# MCU.net
KiCad netlist of a schematic drawn in Altium Designer
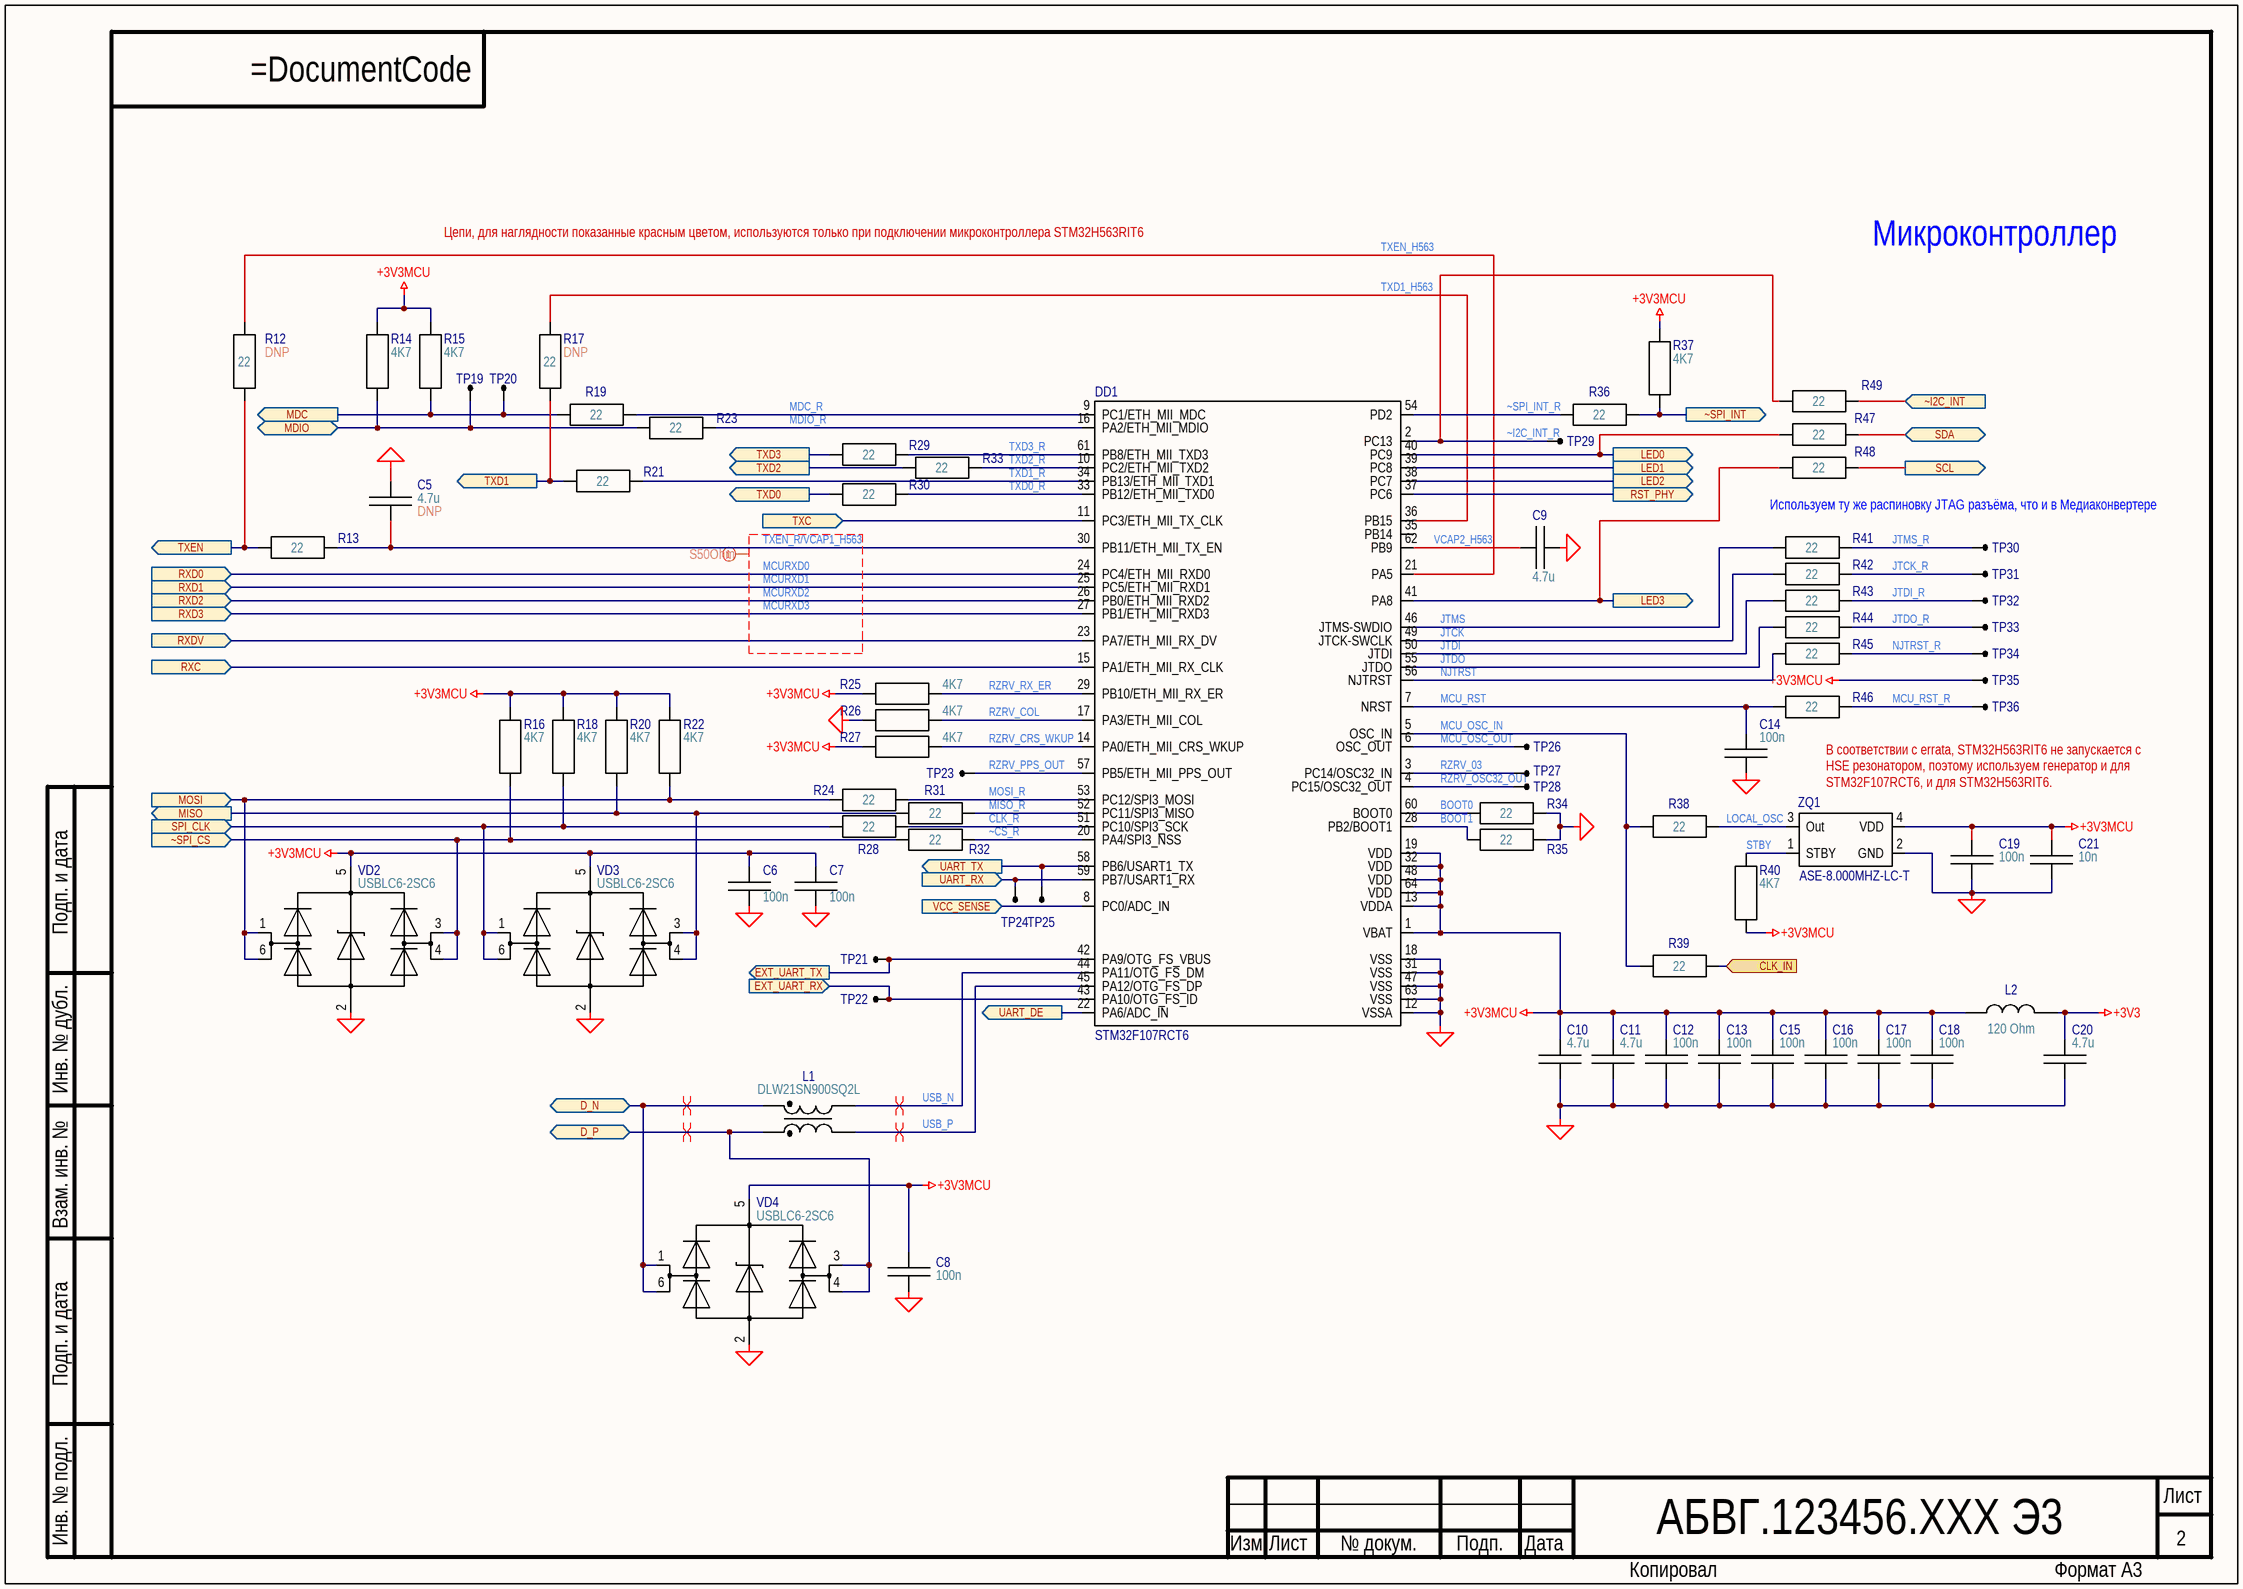
[diagram p0: MCU.SchDoc]

(export (version "E")
  (design (tool "Eeschema 10.0.6"))
  (components
    (comp (ref "C5")
      (value "4.7u")
      (footprint "C0603")
      (description "Чип-конденсатор 4,7 мкФ 10% 16 В X5R 0603")
      (fields
        (field (name "MANUFACTURER PART NUMBER") "CC0603KRX5R7BB475")
        (field (name "MANUFACTURER") "Yageo")
      )
      (libsource (lib "ums") (part "C0603"))
    )
    (comp (ref "C6")
      (value "100n")
      (footprint "C0402")
      (description "Чип-конденсатор 100 нФ 10% 50 В X7R 0402")
      (fields
        (field (name "MANUFACTURER PART NUMBER") "CC0402KRX7R9BB104")
        (field (name "MANUFACTURER") "Yageo")
      )
      (libsource (lib "ums") (part "C0402"))
    )
    (comp (ref "C7")
      (value "100n")
      (footprint "C0402")
      (description "Чип-конденсатор 100 нФ 10% 50 В X7R 0402")
      (fields
        (field (name "MANUFACTURER PART NUMBER") "CC0402KRX7R9BB104")
        (field (name "MANUFACTURER") "Yageo")
      )
      (libsource (lib "ums") (part "C0402"))
    )
    (comp (ref "C8")
      (value "100n")
      (footprint "C0402")
      (description "Чип-конденсатор 100 нФ 10% 50 В X7R 0402")
      (fields
        (field (name "MANUFACTURER PART NUMBER") "CC0402KRX7R9BB104")
        (field (name "MANUFACTURER") "Yageo")
      )
      (libsource (lib "ums") (part "C0402"))
    )
    (comp (ref "C9")
      (value "4.7u")
      (footprint "C0603")
      (description "Чип-конденсатор 4,7 мкФ 10% 16 В X5R 0603")
      (fields
        (field (name "MANUFACTURER PART NUMBER") "CC0603KRX5R7BB475")
        (field (name "MANUFACTURER") "Yageo")
      )
      (libsource (lib "ums") (part "C0603"))
    )
    (comp (ref "C10")
      (value "4.7u")
      (footprint "C0603")
      (description "Чип-конденсатор 4,7 мкФ 10% 16 В X5R 0603")
      (fields
        (field (name "MANUFACTURER PART NUMBER") "CC0603KRX5R7BB475")
        (field (name "MANUFACTURER") "Yageo")
      )
      (libsource (lib "ums") (part "C0603"))
    )
    (comp (ref "C11")
      (value "4.7u")
      (footprint "C0603")
      (description "Чип-конденсатор 4,7 мкФ 10% 16 В X5R 0603")
      (fields
        (field (name "MANUFACTURER PART NUMBER") "CC0603KRX5R7BB475")
        (field (name "MANUFACTURER") "Yageo")
      )
      (libsource (lib "ums") (part "C0603"))
    )
    (comp (ref "C12")
      (value "100n")
      (footprint "C0402")
      (description "Чип-конденсатор 100 нФ 10% 50 В X7R 0402")
      (fields
        (field (name "MANUFACTURER PART NUMBER") "CC0402KRX7R9BB104")
        (field (name "MANUFACTURER") "Yageo")
      )
      (libsource (lib "ums") (part "C0402"))
    )
    (comp (ref "C13")
      (value "100n")
      (footprint "C0402")
      (description "Чип-конденсатор 100 нФ 10% 50 В X7R 0402")
      (fields
        (field (name "MANUFACTURER PART NUMBER") "CC0402KRX7R9BB104")
        (field (name "MANUFACTURER") "Yageo")
      )
      (libsource (lib "ums") (part "C0402"))
    )
    (comp (ref "C14")
      (value "100n")
      (footprint "C0402")
      (description "Чип-конденсатор 100 нФ 10% 50 В X7R 0402")
      (fields
        (field (name "MANUFACTURER PART NUMBER") "CC0402KRX7R9BB104")
        (field (name "MANUFACTURER") "Yageo")
      )
      (libsource (lib "ums") (part "C0402"))
    )
    (comp (ref "C15")
      (value "100n")
      (footprint "C0402")
      (description "Чип-конденсатор 100 нФ 10% 50 В X7R 0402")
      (fields
        (field (name "MANUFACTURER PART NUMBER") "CC0402KRX7R9BB104")
        (field (name "MANUFACTURER") "Yageo")
      )
      (libsource (lib "ums") (part "C0402"))
    )
    (comp (ref "C16")
      (value "100n")
      (footprint "C0402")
      (description "Чип-конденсатор 100 нФ 10% 50 В X7R 0402")
      (fields
        (field (name "MANUFACTURER PART NUMBER") "CC0402KRX7R9BB104")
        (field (name "MANUFACTURER") "Yageo")
      )
      (libsource (lib "ums") (part "C0402"))
    )
    (comp (ref "C17")
      (value "100n")
      (footprint "C0402")
      (description "Чип-конденсатор 100 нФ 10% 50 В X7R 0402")
      (fields
        (field (name "MANUFACTURER PART NUMBER") "CC0402KRX7R9BB104")
        (field (name "MANUFACTURER") "Yageo")
      )
      (libsource (lib "ums") (part "C0402"))
    )
    (comp (ref "C18")
      (value "100n")
      (footprint "C0402")
      (description "Чип-конденсатор 100 нФ 10% 50 В X7R 0402")
      (fields
        (field (name "MANUFACTURER PART NUMBER") "CC0402KRX7R9BB104")
        (field (name "MANUFACTURER") "Yageo")
      )
      (libsource (lib "ums") (part "C0402"))
    )
    (comp (ref "C19")
      (value "100n")
      (footprint "C0402")
      (description "Чип-конденсатор 100 нФ 10% 50 В X7R 0402")
      (fields
        (field (name "MANUFACTURER PART NUMBER") "CC0402KRX7R9BB104")
        (field (name "MANUFACTURER") "Yageo")
      )
      (libsource (lib "ums") (part "C0402"))
    )
    (comp (ref "C20")
      (value "4.7u")
      (footprint "C0603")
      (description "Чип-конденсатор 4,7 мкФ 10% 16 В X5R 0603")
      (fields
        (field (name "MANUFACTURER PART NUMBER") "CC0603KRX5R7BB475")
        (field (name "MANUFACTURER") "Yageo")
      )
      (libsource (lib "ums") (part "C0603"))
    )
    (comp (ref "C21")
      (value "10n")
      (footprint "C0402")
      (description "Чип-конденсатор 10 нФ 10% 50 В X7R 0402")
      (fields
        (field (name "MANUFACTURER PART NUMBER") "CC0402KRX7R9BB103")
        (field (name "MANUFACTURER") "Yageo")
      )
      (libsource (lib "ums") (part "C0402"))
    )
    (comp (ref "DD1")
      (value "STM32F107RCT6")
      (footprint "LQFP-64-STM-Microcontroller")
      (description "Микроконтроллер ARM")
      (fields (field (name "MANUFACTURER") "ST Microelectronics"))
      (libsource (lib "ums") (part "STM32F107RCT6"))
    )
    (comp (ref "L1")
      (value "DLW21SN900SQ2L")
      (footprint "DLW21S")
      (description "Фильтр синфазный DLW21SN900SQ2L")
      (fields (field (name "MANUFACTURER") "Murata"))
      (libsource (lib "ums") (part "DLW21SN900SQ2L"))
    )
    (comp (ref "L2")
      (value "120 Ohm")
      (footprint "BLM18PG")
      (description "Фильтр индуктивный 120 Ом @ 100 МГц 2 А 0603")
      (fields
        (field (name "MANUFACTURER") "FENGHUA Advanced Technology")
        (field (name "MANUFACTURER PART NUMBER") "CBM160808U121T")
      )
      (libsource (lib "ums") (part "BLM18PG121SN1D"))
    )
    (comp (ref "R12")
      (value "22")
      (footprint "R0402")
      (description "Чип-резистор 22 Ом 1% 0402")
      (fields
        (field (name "MANUFACTURER PART NUMBER") "RC0402FR-0722RL")
        (field (name "MANUFACTURER") "Yageo")
      )
      (libsource (lib "ums") (part "R0402_tooth_1"))
    )
    (comp (ref "R13")
      (value "22")
      (footprint "R0402")
      (description "Чип-резистор 22 Ом 1% 0402")
      (fields
        (field (name "MANUFACTURER PART NUMBER") "RC0402FR-0722RL")
        (field (name "MANUFACTURER") "Yageo")
      )
      (libsource (lib "ums") (part "R0402_tooth_1"))
    )
    (comp (ref "R14")
      (value "4K7")
      (footprint "R0402")
      (description "Чип-резистор 4,7 кОм 1% 0402")
      (fields
        (field (name "MANUFACTURER PART NUMBER") "RC0402FR-074K7L")
        (field (name "MANUFACTURER") "Yageo")
      )
      (libsource (lib "ums") (part "R0402"))
    )
    (comp (ref "R15")
      (value "4K7")
      (footprint "R0402")
      (description "Чип-резистор 4,7 кОм 1% 0402")
      (fields
        (field (name "MANUFACTURER PART NUMBER") "RC0402FR-074K7L")
        (field (name "MANUFACTURER") "Yageo")
      )
      (libsource (lib "ums") (part "R0402"))
    )
    (comp (ref "R16")
      (value "4K7")
      (footprint "R0402")
      (description "Чип-резистор 4,7 кОм 1% 0402")
      (fields
        (field (name "MANUFACTURER PART NUMBER") "RC0402FR-074K7L")
        (field (name "MANUFACTURER") "Yageo")
      )
      (libsource (lib "ums") (part "R0402"))
    )
    (comp (ref "R17")
      (value "22")
      (footprint "R0402")
      (description "Чип-резистор 22 Ом 1% 0402")
      (fields
        (field (name "MANUFACTURER PART NUMBER") "RC0402FR-0722RL")
        (field (name "MANUFACTURER") "Yageo")
      )
      (libsource (lib "ums") (part "R0402_tooth_1"))
    )
    (comp (ref "R18")
      (value "4K7")
      (footprint "R0402")
      (description "Чип-резистор 4,7 кОм 1% 0402")
      (fields
        (field (name "MANUFACTURER PART NUMBER") "RC0402FR-074K7L")
        (field (name "MANUFACTURER") "Yageo")
      )
      (libsource (lib "ums") (part "R0402"))
    )
    (comp (ref "R19")
      (value "22")
      (footprint "R0402")
      (description "Чип-резистор 22 Ом 1% 0402")
      (fields
        (field (name "MANUFACTURER PART NUMBER") "RC0402FR-0722RL")
        (field (name "MANUFACTURER") "Yageo")
      )
      (libsource (lib "ums") (part "R0402_tooth_1"))
    )
    (comp (ref "R20")
      (value "4K7")
      (footprint "R0402")
      (description "Чип-резистор 4,7 кОм 1% 0402")
      (fields
        (field (name "MANUFACTURER PART NUMBER") "RC0402FR-074K7L")
        (field (name "MANUFACTURER") "Yageo")
      )
      (libsource (lib "ums") (part "R0402"))
    )
    (comp (ref "R21")
      (value "22")
      (footprint "R0402")
      (description "Чип-резистор 22 Ом 1% 0402")
      (fields
        (field (name "MANUFACTURER PART NUMBER") "RC0402FR-0722RL")
        (field (name "MANUFACTURER") "Yageo")
      )
      (libsource (lib "ums") (part "R0402_tooth_1"))
    )
    (comp (ref "R22")
      (value "4K7")
      (footprint "R0402")
      (description "Чип-резистор 4,7 кОм 1% 0402")
      (fields
        (field (name "MANUFACTURER PART NUMBER") "RC0402FR-074K7L")
        (field (name "MANUFACTURER") "Yageo")
      )
      (libsource (lib "ums") (part "R0402"))
    )
    (comp (ref "R23")
      (value "22")
      (footprint "R0402")
      (description "Чип-резистор 22 Ом 1% 0402")
      (fields
        (field (name "MANUFACTURER PART NUMBER") "RC0402FR-0722RL")
        (field (name "MANUFACTURER") "Yageo")
      )
      (libsource (lib "ums") (part "R0402_tooth_1"))
    )
    (comp (ref "R24")
      (value "22")
      (footprint "R0402")
      (description "Чип-резистор 22 Ом 1% 0402")
      (fields
        (field (name "MANUFACTURER PART NUMBER") "RC0402FR-0722RL")
        (field (name "MANUFACTURER") "Yageo")
      )
      (libsource (lib "ums") (part "R0402_tooth_1"))
    )
    (comp (ref "R25")
      (value "4K7")
      (footprint "R0402")
      (description "Чип-резистор 4,7 кОм 1% 0402")
      (fields
        (field (name "MANUFACTURER PART NUMBER") "RC0402FR-074K7L")
        (field (name "MANUFACTURER") "Yageo")
      )
      (libsource (lib "ums") (part "R0402"))
    )
    (comp (ref "R26")
      (value "4K7")
      (footprint "R0402")
      (description "Чип-резистор 4,7 кОм 1% 0402")
      (fields
        (field (name "MANUFACTURER PART NUMBER") "RC0402FR-074K7L")
        (field (name "MANUFACTURER") "Yageo")
      )
      (libsource (lib "ums") (part "R0402"))
    )
    (comp (ref "R27")
      (value "4K7")
      (footprint "R0402")
      (description "Чип-резистор 4,7 кОм 1% 0402")
      (fields
        (field (name "MANUFACTURER PART NUMBER") "RC0402FR-074K7L")
        (field (name "MANUFACTURER") "Yageo")
      )
      (libsource (lib "ums") (part "R0402"))
    )
    (comp (ref "R28")
      (value "22")
      (footprint "R0402")
      (description "Чип-резистор 22 Ом 1% 0402")
      (fields
        (field (name "MANUFACTURER PART NUMBER") "RC0402FR-0722RL")
        (field (name "MANUFACTURER") "Yageo")
      )
      (libsource (lib "ums") (part "R0402_tooth_1"))
    )
    (comp (ref "R29")
      (value "22")
      (footprint "R0402")
      (description "Чип-резистор 22 Ом 1% 0402")
      (fields
        (field (name "MANUFACTURER PART NUMBER") "RC0402FR-0722RL")
        (field (name "MANUFACTURER") "Yageo")
      )
      (libsource (lib "ums") (part "R0402_tooth_1"))
    )
    (comp (ref "R30")
      (value "22")
      (footprint "R0402")
      (description "Чип-резистор 22 Ом 1% 0402")
      (fields
        (field (name "MANUFACTURER PART NUMBER") "RC0402FR-0722RL")
        (field (name "MANUFACTURER") "Yageo")
      )
      (libsource (lib "ums") (part "R0402_tooth_1"))
    )
    (comp (ref "R31")
      (value "22")
      (footprint "R0402")
      (description "Чип-резистор 22 Ом 1% 0402")
      (fields
        (field (name "MANUFACTURER PART NUMBER") "RC0402FR-0722RL")
        (field (name "MANUFACTURER") "Yageo")
      )
      (libsource (lib "ums") (part "R0402_tooth_1"))
    )
    (comp (ref "R32")
      (value "22")
      (footprint "R0402")
      (description "Чип-резистор 22 Ом 1% 0402")
      (fields
        (field (name "MANUFACTURER PART NUMBER") "RC0402FR-0722RL")
        (field (name "MANUFACTURER") "Yageo")
      )
      (libsource (lib "ums") (part "R0402_tooth_1"))
    )
    (comp (ref "R33")
      (value "22")
      (footprint "R0402")
      (description "Чип-резистор 22 Ом 1% 0402")
      (fields
        (field (name "MANUFACTURER PART NUMBER") "RC0402FR-0722RL")
        (field (name "MANUFACTURER") "Yageo")
      )
      (libsource (lib "ums") (part "R0402_tooth_1"))
    )
    (comp (ref "R34")
      (value "22")
      (footprint "R0402")
      (description "Чип-резистор 22 Ом 1% 0402")
      (fields
        (field (name "MANUFACTURER PART NUMBER") "RC0402FR-0722RL")
        (field (name "MANUFACTURER") "Yageo")
      )
      (libsource (lib "ums") (part "R0402_tooth_1"))
    )
    (comp (ref "R35")
      (value "22")
      (footprint "R0402")
      (description "Чип-резистор 22 Ом 1% 0402")
      (fields
        (field (name "MANUFACTURER PART NUMBER") "RC0402FR-0722RL")
        (field (name "MANUFACTURER") "Yageo")
      )
      (libsource (lib "ums") (part "R0402_tooth_1"))
    )
    (comp (ref "R36")
      (value "22")
      (footprint "R0402")
      (description "Чип-резистор 22 Ом 1% 0402")
      (fields
        (field (name "MANUFACTURER PART NUMBER") "RC0402FR-0722RL")
        (field (name "MANUFACTURER") "Yageo")
      )
      (libsource (lib "ums") (part "R0402_tooth_1"))
    )
    (comp (ref "R37")
      (value "4K7")
      (footprint "R0402")
      (description "Чип-резистор 4,7 кОм 1% 0402")
      (fields
        (field (name "MANUFACTURER PART NUMBER") "RC0402FR-074K7L")
        (field (name "MANUFACTURER") "Yageo")
      )
      (libsource (lib "ums") (part "R0402"))
    )
    (comp (ref "R38")
      (value "22")
      (footprint "R0402")
      (description "Чип-резистор 22 Ом 1% 0402")
      (fields
        (field (name "MANUFACTURER PART NUMBER") "RC0402FR-0722RL")
        (field (name "MANUFACTURER") "Yageo")
      )
      (libsource (lib "ums") (part "R0402_tooth_1"))
    )
    (comp (ref "R39")
      (value "22")
      (footprint "R0402")
      (description "Чип-резистор 22 Ом 1% 0402")
      (fields
        (field (name "MANUFACTURER PART NUMBER") "RC0402FR-0722RL")
        (field (name "MANUFACTURER") "Yageo")
      )
      (libsource (lib "ums") (part "R0402_tooth_1"))
    )
    (comp (ref "R40")
      (value "4K7")
      (footprint "R0402")
      (description "Чип-резистор 4,7 кОм 1% 0402")
      (fields
        (field (name "MANUFACTURER PART NUMBER") "RC0402FR-074K7L")
        (field (name "MANUFACTURER") "Yageo")
      )
      (libsource (lib "ums") (part "R0402"))
    )
    (comp (ref "R41")
      (value "22")
      (footprint "R0402")
      (description "Чип-резистор 22 Ом 1% 0402")
      (fields
        (field (name "MANUFACTURER PART NUMBER") "RC0402FR-0722RL")
        (field (name "MANUFACTURER") "Yageo")
      )
      (libsource (lib "ums") (part "R0402_tooth_1"))
    )
    (comp (ref "R42")
      (value "22")
      (footprint "R0402")
      (description "Чип-резистор 22 Ом 1% 0402")
      (fields
        (field (name "MANUFACTURER PART NUMBER") "RC0402FR-0722RL")
        (field (name "MANUFACTURER") "Yageo")
      )
      (libsource (lib "ums") (part "R0402_tooth_1"))
    )
    (comp (ref "R43")
      (value "22")
      (footprint "R0402")
      (description "Чип-резистор 22 Ом 1% 0402")
      (fields
        (field (name "MANUFACTURER PART NUMBER") "RC0402FR-0722RL")
        (field (name "MANUFACTURER") "Yageo")
      )
      (libsource (lib "ums") (part "R0402_tooth_1"))
    )
    (comp (ref "R44")
      (value "22")
      (footprint "R0402")
      (description "Чип-резистор 22 Ом 1% 0402")
      (fields
        (field (name "MANUFACTURER PART NUMBER") "RC0402FR-0722RL")
        (field (name "MANUFACTURER") "Yageo")
      )
      (libsource (lib "ums") (part "R0402_tooth_1"))
    )
    (comp (ref "R45")
      (value "22")
      (footprint "R0402")
      (description "Чип-резистор 22 Ом 1% 0402")
      (fields
        (field (name "MANUFACTURER PART NUMBER") "RC0402FR-0722RL")
        (field (name "MANUFACTURER") "Yageo")
      )
      (libsource (lib "ums") (part "R0402_tooth_1"))
    )
    (comp (ref "R46")
      (value "22")
      (footprint "R0402")
      (description "Чип-резистор 22 Ом 1% 0402")
      (fields
        (field (name "MANUFACTURER PART NUMBER") "RC0402FR-0722RL")
        (field (name "MANUFACTURER") "Yageo")
      )
      (libsource (lib "ums") (part "R0402_tooth_1"))
    )
    (comp (ref "R47")
      (value "22")
      (footprint "R0402")
      (description "Чип-резистор 22 Ом 1% 0402")
      (fields
        (field (name "MANUFACTURER PART NUMBER") "RC0402FR-0722RL")
        (field (name "MANUFACTURER") "Yageo")
      )
      (libsource (lib "ums") (part "R0402_tooth_1"))
    )
    (comp (ref "R48")
      (value "22")
      (footprint "R0402")
      (description "Чип-резистор 22 Ом 1% 0402")
      (fields
        (field (name "MANUFACTURER PART NUMBER") "RC0402FR-0722RL")
        (field (name "MANUFACTURER") "Yageo")
      )
      (libsource (lib "ums") (part "R0402_tooth_1"))
    )
    (comp (ref "R49")
      (value "22")
      (footprint "R0402")
      (description "Чип-резистор 22 Ом 1% 0402")
      (fields
        (field (name "MANUFACTURER PART NUMBER") "RC0402FR-0722RL")
        (field (name "MANUFACTURER") "Yageo")
      )
      (libsource (lib "ums") (part "R0402_tooth_1"))
    )
    (comp (ref "TP19")
      (value "TEST_POINT_1.27_STEP")
      (footprint "TEST_POINT_1.27_STEP")
      (description "Контрольная точка SMD")
      (libsource (lib "ums") (part "TEST_POINT_1.27_STEP"))
    )
    (comp (ref "TP20")
      (value "TEST_POINT_1.27_STEP")
      (footprint "TEST_POINT_1.27_STEP")
      (description "Контрольная точка SMD")
      (libsource (lib "ums") (part "TEST_POINT_1.27_STEP"))
    )
    (comp (ref "TP21")
      (value "TEST_POINT_1.27_STEP")
      (footprint "TEST_POINT_1.27_STEP")
      (description "Контрольная точка SMD")
      (libsource (lib "ums") (part "TEST_POINT_1.27_STEP"))
    )
    (comp (ref "TP22")
      (value "TEST_POINT_1.27_STEP")
      (footprint "TEST_POINT_1.27_STEP")
      (description "Контрольная точка SMD")
      (libsource (lib "ums") (part "TEST_POINT_1.27_STEP"))
    )
    (comp (ref "TP23")
      (value "TEST_POINT_SMD")
      (footprint "TEST_POINT_SMD")
      (description "Контрольная точка SMD")
      (libsource (lib "ums") (part "TEST_POINT_SMD"))
    )
    (comp (ref "TP24")
      (value "TEST_POINT_SMD")
      (footprint "TEST_POINT_SMD")
      (description "Контрольная точка SMD")
      (libsource (lib "ums") (part "TEST_POINT_SMD"))
    )
    (comp (ref "TP25")
      (value "TEST_POINT_SMD")
      (footprint "TEST_POINT_SMD")
      (description "Контрольная точка SMD")
      (libsource (lib "ums") (part "TEST_POINT_SMD"))
    )
    (comp (ref "TP26")
      (value "TEST_POINT_SMD")
      (footprint "TEST_POINT_SMD")
      (description "Контрольная точка SMD")
      (libsource (lib "ums") (part "TEST_POINT_SMD"))
    )
    (comp (ref "TP27")
      (value "TEST_POINT_SMD")
      (footprint "TEST_POINT_SMD")
      (description "Контрольная точка SMD")
      (libsource (lib "ums") (part "TEST_POINT_SMD"))
    )
    (comp (ref "TP28")
      (value "TEST_POINT_SMD")
      (footprint "TEST_POINT_SMD")
      (description "Контрольная точка SMD")
      (libsource (lib "ums") (part "TEST_POINT_SMD"))
    )
    (comp (ref "TP29")
      (value "TEST_POINT_SMD")
      (footprint "TEST_POINT_SMD")
      (description "Контрольная точка SMD")
      (libsource (lib "ums") (part "TEST_POINT_SMD"))
    )
    (comp (ref "TP30")
      (value "TEST_POINT_1.27_STEP")
      (footprint "TEST_POINT_1.27_STEP")
      (description "Контрольная точка SMD")
      (libsource (lib "ums") (part "TEST_POINT_1.27_STEP"))
    )
    (comp (ref "TP31")
      (value "TEST_POINT_1.27_STEP")
      (footprint "TEST_POINT_1.27_STEP")
      (description "Контрольная точка SMD")
      (libsource (lib "ums") (part "TEST_POINT_1.27_STEP"))
    )
    (comp (ref "TP32")
      (value "TEST_POINT_1.27_STEP")
      (footprint "TEST_POINT_1.27_STEP")
      (description "Контрольная точка SMD")
      (libsource (lib "ums") (part "TEST_POINT_1.27_STEP"))
    )
    (comp (ref "TP33")
      (value "TEST_POINT_1.27_STEP")
      (footprint "TEST_POINT_1.27_STEP")
      (description "Контрольная точка SMD")
      (libsource (lib "ums") (part "TEST_POINT_1.27_STEP"))
    )
    (comp (ref "TP34")
      (value "TEST_POINT_1.27_STEP")
      (footprint "TEST_POINT_1.27_STEP")
      (description "Контрольная точка SMD")
      (libsource (lib "ums") (part "TEST_POINT_1.27_STEP"))
    )
    (comp (ref "TP35")
      (value "TEST_POINT_1.27_STEP")
      (footprint "TEST_POINT_1.27_STEP")
      (description "Контрольная точка SMD")
      (libsource (lib "ums") (part "TEST_POINT_1.27_STEP"))
    )
    (comp (ref "TP36")
      (value "TEST_POINT_1.27_STEP")
      (footprint "TEST_POINT_1.27_STEP")
      (description "Контрольная точка SMD")
      (libsource (lib "ums") (part "TEST_POINT_1.27_STEP"))
    )
    (comp (ref "VD2")
      (value "USBLC6-2SC6")
      (footprint "SOT-23-6-USBLC-Internal-Jumpers")
      (description "Диодная сборка ESD защиты USBLC6-2SC6")
      (fields (field (name "MANUFACTURER") "UMW"))
      (libsource (lib "ums") (part "USBLC6-2SC6"))
    )
    (comp (ref "VD3")
      (value "USBLC6-2SC6")
      (footprint "SOT-23-6-USBLC-Internal-Jumpers")
      (description "Диодная сборка ESD защиты USBLC6-2SC6")
      (fields (field (name "MANUFACTURER") "UMW"))
      (libsource (lib "ums") (part "USBLC6-2SC6"))
    )
    (comp (ref "VD4")
      (value "USBLC6-2SC6")
      (footprint "SOT-23-6-USBLC-Internal-Jumpers")
      (description "Диодная сборка ESD защиты USBLC6-2SC6")
      (fields (field (name "MANUFACTURER") "UMW"))
      (libsource (lib "ums") (part "USBLC6-2SC6"))
    )
    (comp (ref "ZQ1")
      (value "ASE-8.000MHZ-LC-T")
      (footprint "ASE-X.XXXMHz")
      (description "Резонатор кварцевый 8.0 МГц")
      (fields (field (name "MANUFACTURER") "Abracon"))
      (libsource (lib "ums") (part "ASE-8.000MHZ-LC-T"))
    )
  )
  (nets
    (net (code "1") (name "+3V3") (class "Default")
      (node (ref "C20") (pin "1") (pinfunction "1_1") (pintype "passive"))
      (node (ref "L2") (pin "2") (pinfunction "2_2") (pintype "passive"))
    )
    (net (code "2") (name "+3V3MCU") (class "Default")
      (node (ref "C10") (pin "1") (pinfunction "1_1") (pintype "passive"))
      (node (ref "C11") (pin "1") (pinfunction "1_1") (pintype "passive"))
      (node (ref "C12") (pin "2") (pinfunction "2_2") (pintype "passive"))
      (node (ref "C13") (pin "2") (pinfunction "2_2") (pintype "passive"))
      (node (ref "C15") (pin "2") (pinfunction "2_2") (pintype "passive"))
      (node (ref "C16") (pin "2") (pinfunction "2_2") (pintype "passive"))
      (node (ref "C17") (pin "2") (pinfunction "2_2") (pintype "passive"))
      (node (ref "C18") (pin "2") (pinfunction "2_2") (pintype "passive"))
      (node (ref "C19") (pin "2") (pinfunction "2_2") (pintype "passive"))
      (node (ref "C21") (pin "2") (pinfunction "2_2") (pintype "passive"))
      (node (ref "C6") (pin "2") (pinfunction "2_2") (pintype "passive"))
      (node (ref "C7") (pin "2") (pinfunction "2_2") (pintype "passive"))
      (node (ref "C8") (pin "2") (pinfunction "2_2") (pintype "passive"))
      (node (ref "DD1") (pin "1") (pinfunction "VBAT_1") (pintype "passive"))
      (node (ref "DD1") (pin "13") (pinfunction "VDDA_13") (pintype "passive"))
      (node (ref "DD1") (pin "19") (pinfunction "VDD_19") (pintype "passive"))
      (node (ref "DD1") (pin "32") (pinfunction "VDD_32") (pintype "passive"))
      (node (ref "DD1") (pin "48") (pinfunction "VDD_48") (pintype "passive"))
      (node (ref "DD1") (pin "64") (pinfunction "VDD_64") (pintype "passive"))
      (node (ref "L2") (pin "1") (pinfunction "1_1") (pintype "passive"))
      (node (ref "R14") (pin "2") (pinfunction "2_2") (pintype "passive"))
      (node (ref "R15") (pin "2") (pinfunction "2_2") (pintype "passive"))
      (node (ref "R16") (pin "2") (pinfunction "2_2") (pintype "passive"))
      (node (ref "R18") (pin "2") (pinfunction "2_2") (pintype "passive"))
      (node (ref "R20") (pin "2") (pinfunction "2_2") (pintype "passive"))
      (node (ref "R22") (pin "2") (pinfunction "2_2") (pintype "passive"))
      (node (ref "R25") (pin "2") (pinfunction "2_2") (pintype "passive"))
      (node (ref "R27") (pin "2") (pinfunction "2_2") (pintype "passive"))
      (node (ref "R37") (pin "2") (pinfunction "2_2") (pintype "passive"))
      (node (ref "R40") (pin "1") (pinfunction "1_1") (pintype "passive"))
      (node (ref "TP35") (pin "1") (pinfunction "1_1") (pintype "passive"))
      (node (ref "VD2") (pin "5") (pinfunction "5_5") (pintype "passive"))
      (node (ref "VD3") (pin "5") (pinfunction "5_5") (pintype "passive"))
      (node (ref "VD4") (pin "5") (pinfunction "5_5") (pintype "passive"))
      (node (ref "ZQ1") (pin "4") (pinfunction "VDD_4") (pintype "passive"))
    )
    (net (code "4") (name "/BOOT0") (class "Default")
      (node (ref "DD1") (pin "60") (pinfunction "BOOT0_60") (pintype "passive"))
      (node (ref "R34") (pin "2") (pinfunction "2_2") (pintype "passive"))
    )
    (net (code "5") (name "/BOOT1") (class "Default")
      (node (ref "DD1") (pin "28") (pinfunction "PB2/BOOT1_28") (pintype "passive"))
      (node (ref "R35") (pin "2") (pinfunction "2_2") (pintype "passive"))
    )
    (net (code "6") (name "/CLK_IN") (class "Default")
      (node (ref "R39") (pin "1") (pinfunction "1_1") (pintype "passive"))
    )
    (net (code "7") (name "/CLK_R") (class "Default")
      (node (ref "DD1") (pin "51") (pinfunction "PC10/SPI3_SCK_51") (pintype "passive"))
      (node (ref "R28") (pin "1") (pinfunction "1_1") (pintype "passive"))
    )
    (net (code "8") (name "/D_N") (class "Default")
      (node (ref "L1") (pin "1") (pinfunction "1_1") (pintype "passive"))
      (node (ref "VD4") (pin "1") (pinfunction "1_1") (pintype "passive"))
      (node (ref "VD4") (pin "6") (pinfunction "6_6") (pintype "passive"))
    )
    (net (code "9") (name "/D_P") (class "Default")
      (node (ref "L1") (pin "4") (pinfunction "4_4") (pintype "passive"))
      (node (ref "VD4") (pin "3") (pinfunction "3_3") (pintype "passive"))
      (node (ref "VD4") (pin "4") (pinfunction "4_4") (pintype "passive"))
    )
    (net (code "10") (name "/EXT_UART_RX") (class "Default")
      (node (ref "DD1") (pin "43") (pinfunction "PA10/OTG_FS_ID_43") (pintype "passive"))
      (node (ref "TP22") (pin "1") (pinfunction "1_1") (pintype "passive"))
    )
    (net (code "11") (name "/EXT_UART_TX") (class "Default")
      (node (ref "DD1") (pin "42") (pinfunction "PA9/OTG_FS_VBUS_42") (pintype "passive"))
      (node (ref "TP21") (pin "1") (pinfunction "1_1") (pintype "passive"))
    )
    (net (code "12") (name "/JTCK") (class "Default")
      (node (ref "DD1") (pin "49") (pinfunction "JTCK-SWCLK_49") (pintype "passive"))
      (node (ref "R42") (pin "2") (pinfunction "2_2") (pintype "passive"))
    )
    (net (code "13") (name "/JTCK_R") (class "Default")
      (node (ref "R42") (pin "1") (pinfunction "1_1") (pintype "passive"))
      (node (ref "TP31") (pin "1") (pinfunction "1_1") (pintype "passive"))
    )
    (net (code "14") (name "/JTDI") (class "Default")
      (node (ref "DD1") (pin "50") (pinfunction "JTDI_50") (pintype "passive"))
      (node (ref "R43") (pin "2") (pinfunction "2_2") (pintype "passive"))
    )
    (net (code "15") (name "/JTDI_R") (class "Default")
      (node (ref "R43") (pin "1") (pinfunction "1_1") (pintype "passive"))
      (node (ref "TP32") (pin "1") (pinfunction "1_1") (pintype "passive"))
    )
    (net (code "16") (name "/JTDO") (class "Default")
      (node (ref "DD1") (pin "55") (pinfunction "JTDO_55") (pintype "passive"))
      (node (ref "R44") (pin "2") (pinfunction "2_2") (pintype "passive"))
    )
    (net (code "17") (name "/JTDO_R") (class "Default")
      (node (ref "R44") (pin "1") (pinfunction "1_1") (pintype "passive"))
      (node (ref "TP33") (pin "1") (pinfunction "1_1") (pintype "passive"))
    )
    (net (code "18") (name "/JTMS") (class "Default")
      (node (ref "DD1") (pin "46") (pinfunction "JTMS-SWDIO_46") (pintype "passive"))
      (node (ref "R41") (pin "2") (pinfunction "2_2") (pintype "passive"))
    )
    (net (code "19") (name "/JTMS_R") (class "Default")
      (node (ref "R41") (pin "1") (pinfunction "1_1") (pintype "passive"))
      (node (ref "TP30") (pin "1") (pinfunction "1_1") (pintype "passive"))
    )
    (net (code "20") (name "/LED0") (class "Default")
      (node (ref "DD1") (pin "40") (pinfunction "PC9_40") (pintype "passive"))
      (node (ref "R47") (pin "2") (pinfunction "2_2") (pintype "passive"))
    )
    (net (code "21") (name "/LED1") (class "Default")
      (node (ref "DD1") (pin "39") (pinfunction "PC8_39") (pintype "passive"))
    )
    (net (code "22") (name "/LED2") (class "Default")
      (node (ref "DD1") (pin "38") (pinfunction "PC7_38") (pintype "passive"))
    )
    (net (code "23") (name "/LED3") (class "Default")
      (node (ref "DD1") (pin "41") (pinfunction "PA8_41") (pintype "passive"))
      (node (ref "R48") (pin "2") (pinfunction "2_2") (pintype "passive"))
    )
    (net (code "24") (name "/LOCAL_OSC") (class "Default")
      (node (ref "R38") (pin "1") (pinfunction "1_1") (pintype "passive"))
      (node (ref "ZQ1") (pin "3") (pinfunction "Out_3") (pintype "passive"))
    )
    (net (code "25") (name "/MCURXD0") (class "Default")
      (node (ref "DD1") (pin "24") (pinfunction "PC4/ETH_MII_RXD0_24") (pintype "passive"))
    )
    (net (code "26") (name "/MCURXD1") (class "Default")
      (node (ref "DD1") (pin "25") (pinfunction "PC5/ETH_MII_RXD1_25") (pintype "passive"))
    )
    (net (code "27") (name "/MCURXD2") (class "Default")
      (node (ref "DD1") (pin "26") (pinfunction "PB0/ETH_MII_RXD2_26") (pintype "passive"))
    )
    (net (code "28") (name "/MCURXD3") (class "Default")
      (node (ref "DD1") (pin "27") (pinfunction "PB1/ETH_MII_RXD3_27") (pintype "passive"))
    )
    (net (code "29") (name "/MCU_OSC_IN") (class "Default")
      (node (ref "DD1") (pin "5") (pinfunction "OSC_IN_5") (pintype "passive"))
      (node (ref "R38") (pin "2") (pinfunction "2_2") (pintype "passive"))
      (node (ref "R39") (pin "2") (pinfunction "2_2") (pintype "passive"))
    )
    (net (code "30") (name "/MCU_OSC_OUT") (class "Default")
      (node (ref "DD1") (pin "6") (pinfunction "OSC_OUT_6") (pintype "passive"))
      (node (ref "TP26") (pin "1") (pinfunction "1_1") (pintype "passive"))
    )
    (net (code "31") (name "/MCU_RST") (class "Default")
      (node (ref "C14") (pin "2") (pinfunction "2_2") (pintype "passive"))
      (node (ref "DD1") (pin "7") (pinfunction "NRST_7") (pintype "passive"))
      (node (ref "R46") (pin "2") (pinfunction "2_2") (pintype "passive"))
    )
    (net (code "32") (name "/MCU_RST_R") (class "Default")
      (node (ref "R46") (pin "1") (pinfunction "1_1") (pintype "passive"))
      (node (ref "TP36") (pin "1") (pinfunction "1_1") (pintype "passive"))
    )
    (net (code "33") (name "/MDC") (class "Default")
      (node (ref "R15") (pin "1") (pinfunction "1_1") (pintype "passive"))
      (node (ref "R19") (pin "2") (pinfunction "2_2") (pintype "passive"))
      (node (ref "TP20") (pin "1") (pinfunction "1_1") (pintype "passive"))
    )
    (net (code "34") (name "/MDC_R") (class "Default")
      (node (ref "DD1") (pin "9") (pinfunction "PC1/ETH_MII_MDC_9") (pintype "passive"))
      (node (ref "R19") (pin "1") (pinfunction "1_1") (pintype "passive"))
    )
    (net (code "35") (name "/MDIO") (class "Default")
      (node (ref "R14") (pin "1") (pinfunction "1_1") (pintype "passive"))
      (node (ref "R23") (pin "2") (pinfunction "2_2") (pintype "passive"))
      (node (ref "TP19") (pin "1") (pinfunction "1_1") (pintype "passive"))
    )
    (net (code "36") (name "/MDIO_R") (class "Default")
      (node (ref "DD1") (pin "16") (pinfunction "PA2/ETH_MII_MDIO_16") (pintype "passive"))
      (node (ref "R23") (pin "1") (pinfunction "1_1") (pintype "passive"))
    )
    (net (code "37") (name "/MISO") (class "Default")
      (node (ref "R20") (pin "1") (pinfunction "1_1") (pintype "passive"))
      (node (ref "R31") (pin "2") (pinfunction "2_2") (pintype "passive"))
      (node (ref "VD3") (pin "3") (pinfunction "3_3") (pintype "passive"))
      (node (ref "VD3") (pin "4") (pinfunction "4_4") (pintype "passive"))
    )
    (net (code "38") (name "/MISO_R") (class "Default")
      (node (ref "DD1") (pin "52") (pinfunction "PC11/SPI3_MISO_52") (pintype "passive"))
      (node (ref "R31") (pin "1") (pinfunction "1_1") (pintype "passive"))
    )
    (net (code "39") (name "/MOSI") (class "Default")
      (node (ref "R22") (pin "1") (pinfunction "1_1") (pintype "passive"))
      (node (ref "R24") (pin "2") (pinfunction "2_2") (pintype "passive"))
      (node (ref "VD2") (pin "1") (pinfunction "1_1") (pintype "passive"))
      (node (ref "VD2") (pin "6") (pinfunction "6_6") (pintype "passive"))
    )
    (net (code "40") (name "/MOSI_R") (class "Default")
      (node (ref "DD1") (pin "53") (pinfunction "PC12/SPI3_MOSI_53") (pintype "passive"))
      (node (ref "R24") (pin "1") (pinfunction "1_1") (pintype "passive"))
    )
    (net (code "41") (name "/NJTRST") (class "Default")
      (node (ref "DD1") (pin "56") (pinfunction "NJTRST_56") (pintype "passive"))
      (node (ref "R45") (pin "2") (pinfunction "2_2") (pintype "passive"))
    )
    (net (code "42") (name "/NJTRST_R") (class "Default")
      (node (ref "R45") (pin "1") (pinfunction "1_1") (pintype "passive"))
      (node (ref "TP34") (pin "1") (pinfunction "1_1") (pintype "passive"))
    )
    (net (code "43") (name "/RST_PHY") (class "Default")
      (node (ref "DD1") (pin "37") (pinfunction "PC6_37") (pintype "passive"))
    )
    (net (code "44") (name "/RXC") (class "Default")
      (node (ref "DD1") (pin "15") (pinfunction "PA1/ETH_MII_RX_CLK_15") (pintype "passive"))
    )
    (net (code "45") (name "/RXDV") (class "Default")
      (node (ref "DD1") (pin "23") (pinfunction "PA7/ETH_MII_RX_DV_23") (pintype "passive"))
    )
    (net (code "46") (name "/RZRV_03") (class "Default")
      (node (ref "DD1") (pin "3") (pinfunction "PC14/OSC32_IN_3") (pintype "passive"))
      (node (ref "TP27") (pin "1") (pinfunction "1_1") (pintype "passive"))
    )
    (net (code "47") (name "/RZRV_COL") (class "Default")
      (node (ref "DD1") (pin "17") (pinfunction "PA3/ETH_MII_COL_17") (pintype "passive"))
      (node (ref "R26") (pin "1") (pinfunction "1_1") (pintype "passive"))
    )
    (net (code "48") (name "/RZRV_CRS_WKUP") (class "Default")
      (node (ref "DD1") (pin "14") (pinfunction "PA0/ETH_MII_CRS_WKUP_14") (pintype "passive"))
      (node (ref "R27") (pin "1") (pinfunction "1_1") (pintype "passive"))
    )
    (net (code "49") (name "/RZRV_OSC32_OUT") (class "Default")
      (node (ref "DD1") (pin "4") (pinfunction "PC15/OSC32_OUT_4") (pintype "passive"))
      (node (ref "TP28") (pin "1") (pinfunction "1_1") (pintype "passive"))
    )
    (net (code "50") (name "/RZRV_PPS_OUT") (class "Default")
      (node (ref "DD1") (pin "57") (pinfunction "PB5/ETH_MII_PPS_OUT_57") (pintype "passive"))
      (node (ref "TP23") (pin "1") (pinfunction "1_1") (pintype "passive"))
    )
    (net (code "51") (name "/RZRV_RX_ER") (class "Default")
      (node (ref "DD1") (pin "29") (pinfunction "PB10/ETH_MII_RX_ER_29") (pintype "passive"))
      (node (ref "R25") (pin "1") (pinfunction "1_1") (pintype "passive"))
    )
    (net (code "52") (name "/SCL") (class "Default")
      (node (ref "R48") (pin "1") (pinfunction "1_1") (pintype "passive"))
    )
    (net (code "53") (name "/SDA") (class "Default")
      (node (ref "R47") (pin "1") (pinfunction "1_1") (pintype "passive"))
    )
    (net (code "54") (name "/SPI_CLK") (class "Default")
      (node (ref "R18") (pin "1") (pinfunction "1_1") (pintype "passive"))
      (node (ref "R28") (pin "2") (pinfunction "2_2") (pintype "passive"))
      (node (ref "VD3") (pin "1") (pinfunction "1_1") (pintype "passive"))
      (node (ref "VD3") (pin "6") (pinfunction "6_6") (pintype "passive"))
    )
    (net (code "55") (name "/STBY") (class "Default")
      (node (ref "R40") (pin "2") (pinfunction "2_2") (pintype "passive"))
      (node (ref "ZQ1") (pin "1") (pinfunction "STBY_1") (pintype "passive"))
    )
    (net (code "56") (name "/TXC") (class "Default")
      (node (ref "DD1") (pin "11") (pinfunction "PC3/ETH_MII_TX_CLK_11") (pintype "passive"))
    )
    (net (code "57") (name "/TXD0") (class "Default")
      (node (ref "R30") (pin "2") (pinfunction "2_2") (pintype "passive"))
    )
    (net (code "58") (name "/TXD0_R") (class "Default")
      (node (ref "DD1") (pin "33") (pinfunction "PB12/ETH_MII_TXD0_33") (pintype "passive"))
      (node (ref "R30") (pin "1") (pinfunction "1_1") (pintype "passive"))
    )
    (net (code "59") (name "/TXD1") (class "Default")
      (node (ref "R17") (pin "1") (pinfunction "1_1") (pintype "passive"))
      (node (ref "R21") (pin "2") (pinfunction "2_2") (pintype "passive"))
    )
    (net (code "60") (name "/TXD1_H563") (class "Default")
      (node (ref "DD1") (pin "36") (pinfunction "PB15_36") (pintype "passive"))
      (node (ref "R17") (pin "2") (pinfunction "2_2") (pintype "passive"))
    )
    (net (code "61") (name "/TXD1_R") (class "Default")
      (node (ref "DD1") (pin "34") (pinfunction "PB13/ETH_MII_TXD1_34") (pintype "passive"))
      (node (ref "R21") (pin "1") (pinfunction "1_1") (pintype "passive"))
    )
    (net (code "62") (name "/TXD2") (class "Default")
      (node (ref "R33") (pin "2") (pinfunction "2_2") (pintype "passive"))
    )
    (net (code "63") (name "/TXD2_R") (class "Default")
      (node (ref "DD1") (pin "10") (pinfunction "PC2/ETH_MII_TXD2_10") (pintype "passive"))
      (node (ref "R33") (pin "1") (pinfunction "1_1") (pintype "passive"))
    )
    (net (code "64") (name "/TXD3") (class "Default")
      (node (ref "R29") (pin "2") (pinfunction "2_2") (pintype "passive"))
    )
    (net (code "65") (name "/TXD3_R") (class "Default")
      (node (ref "DD1") (pin "61") (pinfunction "PB8/ETH_MII_TXD3_61") (pintype "passive"))
      (node (ref "R29") (pin "1") (pinfunction "1_1") (pintype "passive"))
    )
    (net (code "66") (name "/TXEN") (class "Default")
      (node (ref "R12") (pin "1") (pinfunction "1_1") (pintype "passive"))
      (node (ref "R13") (pin "1") (pinfunction "1_1") (pintype "passive"))
    )
    (net (code "67") (name "/TXEN_H563") (class "Default")
      (node (ref "DD1") (pin "21") (pinfunction "PA5_21") (pintype "passive"))
      (node (ref "R12") (pin "2") (pinfunction "2_2") (pintype "passive"))
    )
    (net (code "68") (name "/TXEN_R{slash}VCAP1_H563") (class "Default")
      (node (ref "C5") (pin "2") (pinfunction "2_2") (pintype "passive"))
      (node (ref "DD1") (pin "30") (pinfunction "PB11/ETH_MII_TX_EN_30") (pintype "passive"))
      (node (ref "R13") (pin "2") (pinfunction "2_2") (pintype "passive"))
    )
    (net (code "69") (name "/UART_DE") (class "Default")
      (node (ref "DD1") (pin "22") (pinfunction "PA6/ADC_IN_22") (pintype "passive"))
    )
    (net (code "70") (name "/UART_RX") (class "Default")
      (node (ref "DD1") (pin "59") (pinfunction "PB7/USART1_RX_59") (pintype "passive"))
      (node (ref "TP24") (pin "1") (pinfunction "1_1") (pintype "passive"))
    )
    (net (code "71") (name "/UART_TX") (class "Default")
      (node (ref "DD1") (pin "58") (pinfunction "PB6/USART1_TX_58") (pintype "passive"))
      (node (ref "TP25") (pin "1") (pinfunction "1_1") (pintype "passive"))
    )
    (net (code "72") (name "/USB_N") (class "Default")
      (node (ref "DD1") (pin "44") (pinfunction "PA11/OTG_FS_DM_44") (pintype "passive"))
      (node (ref "L1") (pin "2") (pinfunction "2_2") (pintype "passive"))
    )
    (net (code "73") (name "/USB_P") (class "Default")
      (node (ref "DD1") (pin "45") (pinfunction "PA12/OTG_FS_DP_45") (pintype "passive"))
      (node (ref "L1") (pin "3") (pinfunction "3_3") (pintype "passive"))
    )
    (net (code "74") (name "/VCAP2_H563") (class "Default")
      (node (ref "C9") (pin "1") (pinfunction "1_1") (pintype "passive"))
      (node (ref "DD1") (pin "62") (pinfunction "PB9_62") (pintype "passive"))
    )
    (net (code "75") (name "/VCC_SENSE") (class "Default")
      (node (ref "DD1") (pin "8") (pinfunction "PC0/ADC_IN_8") (pintype "passive"))
    )
    (net (code "76") (name "/~CS_R") (class "Default")
      (node (ref "DD1") (pin "20") (pinfunction "PA4/SPI3_NSS_20") (pintype "passive"))
      (node (ref "R32") (pin "1") (pinfunction "1_1") (pintype "passive"))
    )
    (net (code "77") (name "/~I2C_INT") (class "Default")
      (node (ref "R49") (pin "1") (pinfunction "1_1") (pintype "passive"))
    )
    (net (code "78") (name "/~I2C_INT_R") (class "Default")
      (node (ref "DD1") (pin "2") (pinfunction "PC13_2") (pintype "passive"))
      (node (ref "R49") (pin "2") (pinfunction "2_2") (pintype "passive"))
      (node (ref "TP29") (pin "1") (pinfunction "1_1") (pintype "passive"))
    )
    (net (code "79") (name "/~SPI_CS") (class "Default")
      (node (ref "R16") (pin "1") (pinfunction "1_1") (pintype "passive"))
      (node (ref "R32") (pin "2") (pinfunction "2_2") (pintype "passive"))
      (node (ref "VD2") (pin "3") (pinfunction "3_3") (pintype "passive"))
      (node (ref "VD2") (pin "4") (pinfunction "4_4") (pintype "passive"))
    )
    (net (code "80") (name "/~SPI_INT") (class "Default")
      (node (ref "R36") (pin "1") (pinfunction "1_1") (pintype "passive"))
      (node (ref "R37") (pin "1") (pinfunction "1_1") (pintype "passive"))
    )
    (net (code "81") (name "/~SPI_INT_R") (class "Default")
      (node (ref "DD1") (pin "54") (pinfunction "PD2_54") (pintype "passive"))
      (node (ref "R36") (pin "2") (pinfunction "2_2") (pintype "passive"))
    )
    (net (code "82") (name "GND") (class "Default")
      (node (ref "C10") (pin "2") (pinfunction "2_2") (pintype "passive"))
      (node (ref "C11") (pin "2") (pinfunction "2_2") (pintype "passive"))
      (node (ref "C12") (pin "1") (pinfunction "1_1") (pintype "passive"))
      (node (ref "C13") (pin "1") (pinfunction "1_1") (pintype "passive"))
      (node (ref "C14") (pin "1") (pinfunction "1_1") (pintype "passive"))
      (node (ref "C15") (pin "1") (pinfunction "1_1") (pintype "passive"))
      (node (ref "C16") (pin "1") (pinfunction "1_1") (pintype "passive"))
      (node (ref "C17") (pin "1") (pinfunction "1_1") (pintype "passive"))
      (node (ref "C18") (pin "1") (pinfunction "1_1") (pintype "passive"))
      (node (ref "C19") (pin "1") (pinfunction "1_1") (pintype "passive"))
      (node (ref "C20") (pin "2") (pinfunction "2_2") (pintype "passive"))
      (node (ref "C21") (pin "1") (pinfunction "1_1") (pintype "passive"))
      (node (ref "C5") (pin "1") (pinfunction "1_1") (pintype "passive"))
      (node (ref "C6") (pin "1") (pinfunction "1_1") (pintype "passive"))
      (node (ref "C7") (pin "1") (pinfunction "1_1") (pintype "passive"))
      (node (ref "C8") (pin "1") (pinfunction "1_1") (pintype "passive"))
      (node (ref "C9") (pin "2") (pinfunction "2_2") (pintype "passive"))
      (node (ref "DD1") (pin "12") (pinfunction "VSSA_12") (pintype "passive"))
      (node (ref "DD1") (pin "18") (pinfunction "VSS_18") (pintype "passive"))
      (node (ref "DD1") (pin "31") (pinfunction "VSS_31") (pintype "passive"))
      (node (ref "DD1") (pin "47") (pinfunction "VSS_47") (pintype "passive"))
      (node (ref "DD1") (pin "63") (pinfunction "VSS_63") (pintype "passive"))
      (node (ref "R26") (pin "2") (pinfunction "2_2") (pintype "passive"))
      (node (ref "R34") (pin "1") (pinfunction "1_1") (pintype "passive"))
      (node (ref "R35") (pin "1") (pinfunction "1_1") (pintype "passive"))
      (node (ref "VD2") (pin "2") (pinfunction "2_2") (pintype "passive"))
      (node (ref "VD3") (pin "2") (pinfunction "2_2") (pintype "passive"))
      (node (ref "VD4") (pin "2") (pinfunction "2_2") (pintype "passive"))
      (node (ref "ZQ1") (pin "2") (pinfunction "GND_2") (pintype "passive"))
    )
    (net (code "83") (name "unconnected-(DD1-PB14-Pad35)") (class "Default")
      (node (ref "DD1") (pin "35") (pinfunction "PB14_35") (pintype "passive"))
    )
  )
)
